# kinesis-advantage-v2_5.net
KiCad netlist of a schematic drawn in EAGLE
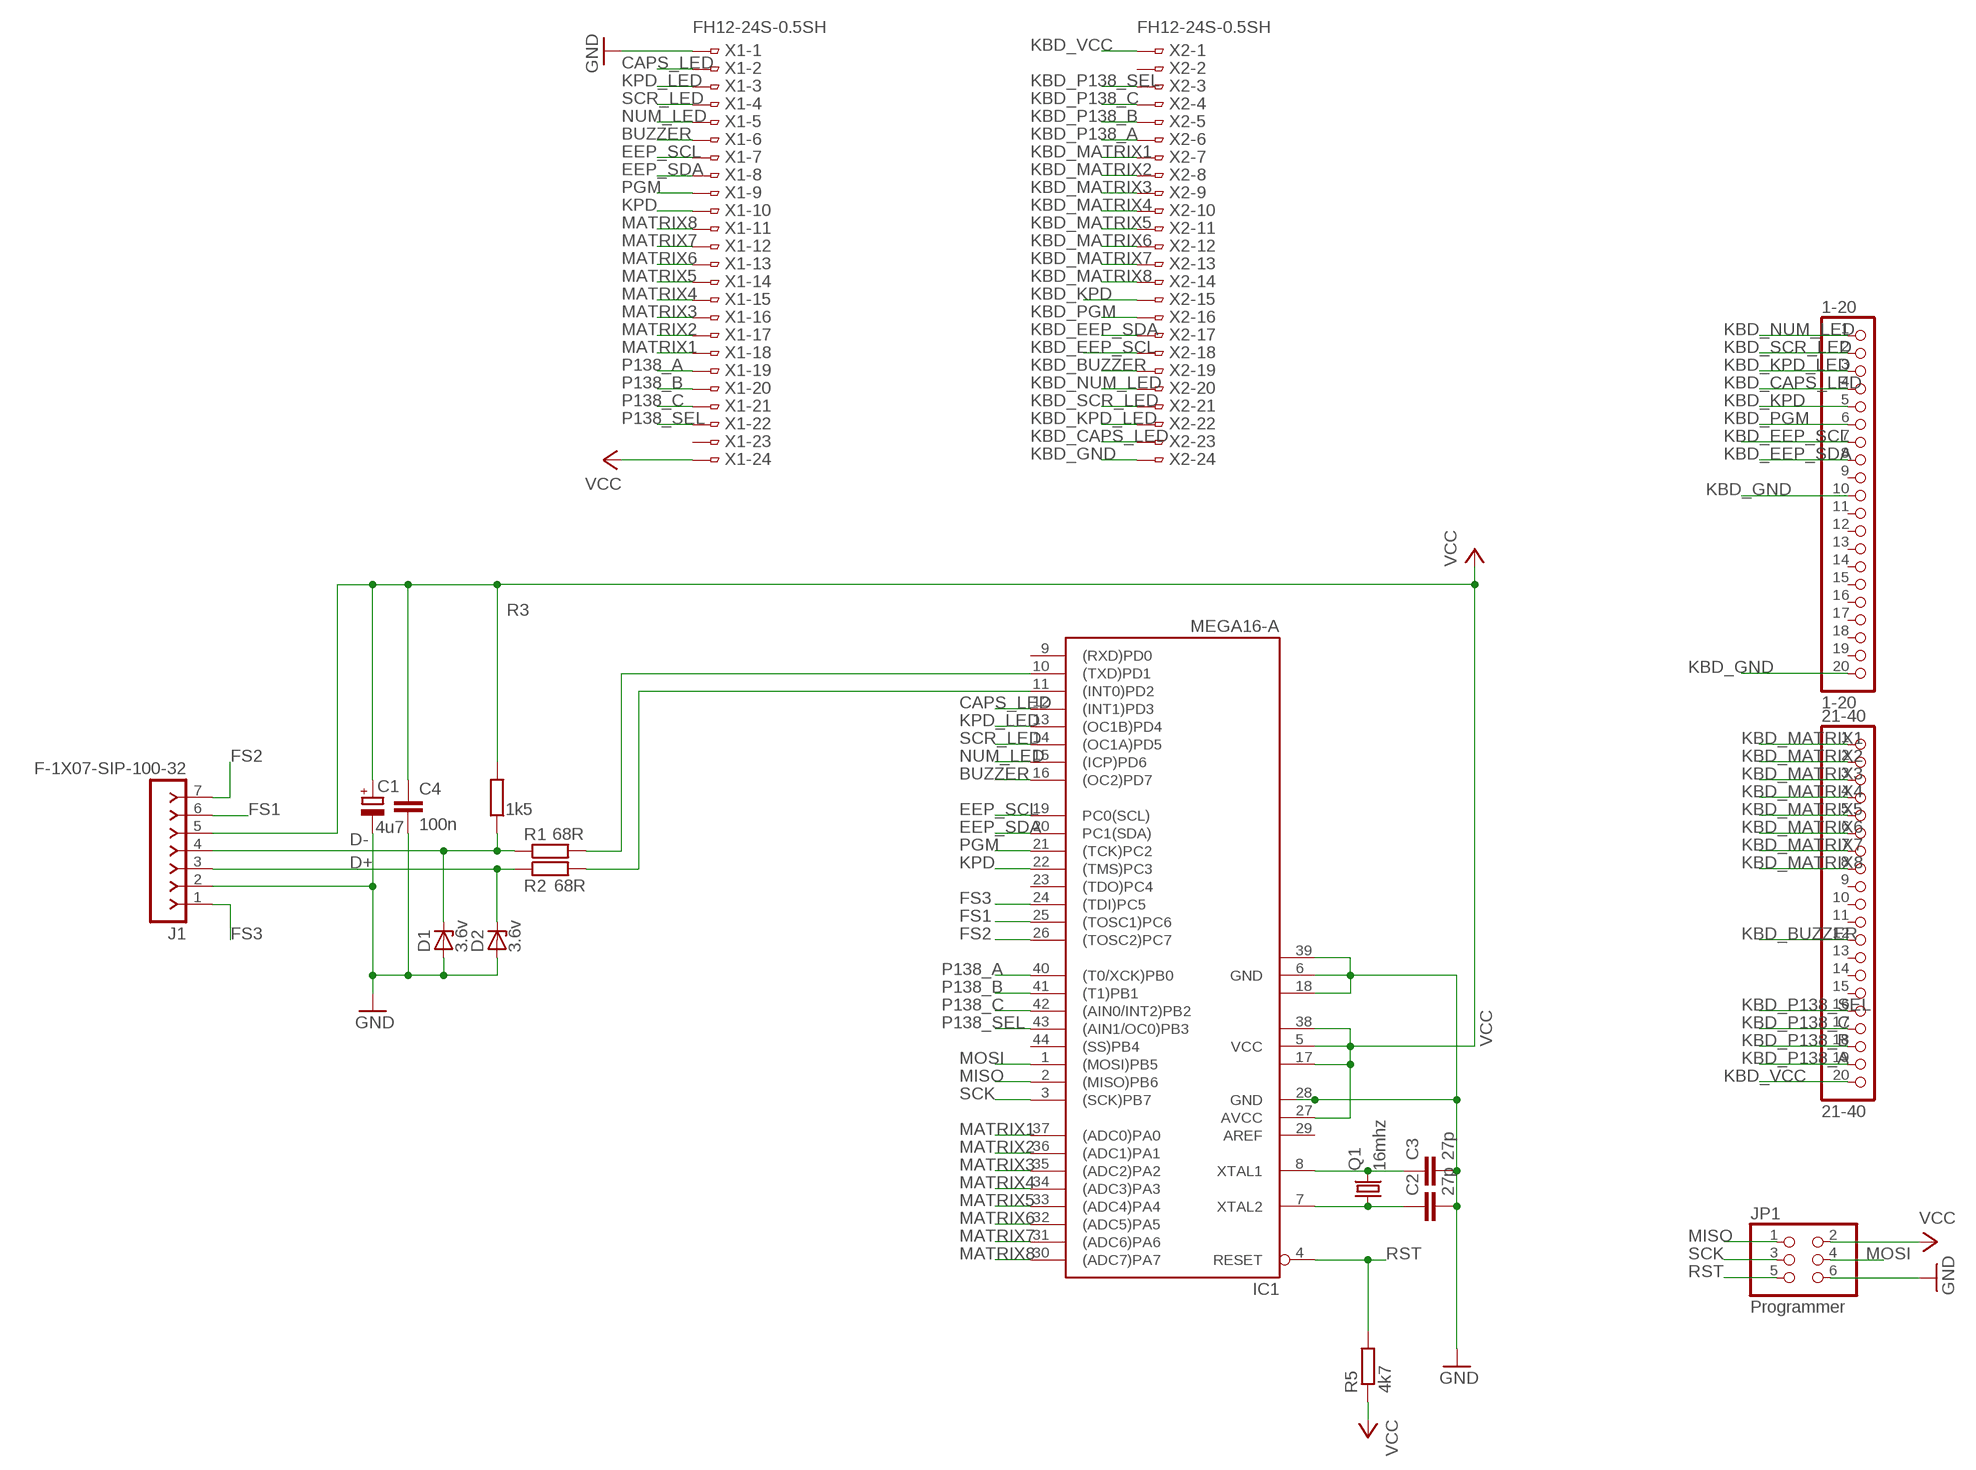
[diagram p0: schematic, sheet 1]

(export (version "E")
  (design (tool "Eeschema 10.0.6"))
  (components
    (comp (ref "1-20")
      (value "1-20")
      (footprint "eagle-import:1X20-BIG")
      (libsource (lib "eagle-import") (part "PINHD-1X20-BIG"))
    )
    (comp (ref "21-40")
      (value "21-40")
      (footprint "eagle-import:1X20-BIG")
      (libsource (lib "eagle-import") (part "PINHD-1X20-BIG"))
    )
    (comp (ref "C1")
      (value "4u7")
      (footprint "eagle-import:E2-5")
      (libsource (lib "eagle-import") (part "CPOL-EUE2-5"))
    )
    (comp (ref "C2")
      (value "27p")
      (footprint "eagle-import:C0603")
      (libsource (lib "eagle-import") (part "C-EUC0603"))
    )
    (comp (ref "C3")
      (value "27p")
      (footprint "eagle-import:C0603")
      (libsource (lib "eagle-import") (part "C-EUC0603"))
    )
    (comp (ref "C4")
      (value "100n")
      (footprint "eagle-import:C0603")
      (libsource (lib "eagle-import") (part "C-EUC0603"))
    )
    (comp (ref "D1")
      (value "3.6v")
      (footprint "eagle-import:SOD80C")
      (libsource (lib "eagle-import") (part "ZENER-DIODESOD80C"))
    )
    (comp (ref "D2")
      (value "3.6v")
      (footprint "eagle-import:SOD80C")
      (libsource (lib "eagle-import") (part "ZENER-DIODESOD80C"))
    )
    (comp (ref "IC1")
      (value "MEGA16-A")
      (footprint "eagle-import:TQFP44")
      (fields (field (name "MPN") "ATMEGA16-16AU"))
      (libsource (lib "eagle-import") (part "MEGA16-A"))
    )
    (comp (ref "J1")
      (value "F-1X07-SIP-100-32")
      (footprint "eagle-import:SIP-100-07-32")
      (libsource (lib "eagle-import") (part "F-1X07-SIP-100-32"))
    )
    (comp (ref "JP1")
      (value "Programmer")
      (footprint "eagle-import:2X03")
      (libsource (lib "eagle-import") (part "PINHD-2X3"))
    )
    (comp (ref "Q1")
      (value "16mhz")
      (footprint "eagle-import:HC49_S")
      (libsource (lib "eagle-import") (part "CRYSTALHC49S"))
    )
    (comp (ref "R1")
      (value "68R")
      (footprint "eagle-import:R0603")
      (libsource (lib "eagle-import") (part "R-EU_R0603"))
    )
    (comp (ref "R2")
      (value "68R")
      (footprint "eagle-import:R0603")
      (libsource (lib "eagle-import") (part "R-EU_R0603"))
    )
    (comp (ref "R3")
      (value "1k5")
      (footprint "eagle-import:R0603")
      (libsource (lib "eagle-import") (part "R-EU_R0603"))
    )
    (comp (ref "R5")
      (value "4k7")
      (footprint "eagle-import:R0603")
      (libsource (lib "eagle-import") (part "R-EU_R0603"))
    )
    (comp (ref "X1")
      (value "FH12-24S-0.5SH")
      (footprint "eagle-import:FH12-24S-0.5SH")
      (fields (field (name "MPN") "FH12-24S-0.5SH(55)"))
      (libsource (lib "eagle-import") (part "FH12-24S-0.5SH"))
    )
    (comp (ref "X2")
      (value "FH12-24S-0.5SH")
      (footprint "eagle-import:FH12-24S-0.5SH")
      (fields (field (name "MPN") "FH12-24S-0.5SH(55)"))
      (libsource (lib "eagle-import") (part "FH12-24S-0.5SH"))
    )
  )
  (nets
    (net (code "1") (name "/BUZZER") (class "Default")
      (node (ref "IC1") (pin "16") (pinfunction "(OC2)PD7_16") (pintype "bidirectional"))
      (node (ref "X1") (pin "6") (pinfunction "1_6") (pintype "passive"))
    )
    (net (code "2") (name "/CAPS_LED") (class "Default")
      (node (ref "IC1") (pin "12") (pinfunction "(INT1)PD3_12") (pintype "bidirectional"))
      (node (ref "X1") (pin "2") (pinfunction "1_2") (pintype "passive"))
    )
    (net (code "3") (name "/D+") (class "Default")
      (node (ref "D2") (pin "C") (pinfunction "C_C") (pintype "passive"))
      (node (ref "J1") (pin "3") (pinfunction "3_3") (pintype "passive"))
      (node (ref "R2") (pin "1") (pinfunction "1_1") (pintype "passive"))
    )
    (net (code "4") (name "/D-") (class "Default")
      (node (ref "D1") (pin "C") (pinfunction "C_C") (pintype "passive"))
      (node (ref "J1") (pin "4") (pinfunction "4_4") (pintype "passive"))
      (node (ref "R1") (pin "1") (pinfunction "1_1") (pintype "passive"))
      (node (ref "R3") (pin "1") (pinfunction "1_1") (pintype "passive"))
    )
    (net (code "5") (name "/EEP_SCL") (class "Default")
      (node (ref "IC1") (pin "19") (pinfunction "PC0(SCL)_19") (pintype "bidirectional"))
      (node (ref "X1") (pin "7") (pinfunction "1_7") (pintype "passive"))
    )
    (net (code "6") (name "/EEP_SDA") (class "Default")
      (node (ref "IC1") (pin "20") (pinfunction "PC1(SDA)_20") (pintype "bidirectional"))
      (node (ref "X1") (pin "8") (pinfunction "1_8") (pintype "passive"))
    )
    (net (code "7") (name "/FS1") (class "Default")
      (node (ref "IC1") (pin "25") (pinfunction "(TOSC1)PC6_25") (pintype "bidirectional"))
      (node (ref "J1") (pin "6") (pinfunction "6_6") (pintype "passive"))
    )
    (net (code "8") (name "/FS2") (class "Default")
      (node (ref "IC1") (pin "26") (pinfunction "(TOSC2)PC7_26") (pintype "bidirectional"))
      (node (ref "J1") (pin "7") (pinfunction "7_7") (pintype "passive"))
    )
    (net (code "9") (name "/FS3") (class "Default")
      (node (ref "IC1") (pin "24") (pinfunction "(TDI)PC5_24") (pintype "bidirectional"))
      (node (ref "J1") (pin "1") (pinfunction "1_1") (pintype "passive"))
    )
    (net (code "10") (name "/KBD_BUZZER") (class "Default")
      (node (ref "21-40") (pin "12") (pinfunction "12_12") (pintype "passive"))
      (node (ref "X2") (pin "19") (pinfunction "1_19") (pintype "passive"))
    )
    (net (code "11") (name "/KBD_CAPS_LED") (class "Default")
      (node (ref "1-20") (pin "4") (pinfunction "4_4") (pintype "passive"))
      (node (ref "X2") (pin "23") (pinfunction "1_23") (pintype "passive"))
    )
    (net (code "12") (name "/KBD_EEP_SCL") (class "Default")
      (node (ref "1-20") (pin "7") (pinfunction "7_7") (pintype "passive"))
      (node (ref "X2") (pin "18") (pinfunction "1_18") (pintype "passive"))
    )
    (net (code "13") (name "/KBD_EEP_SDA") (class "Default")
      (node (ref "1-20") (pin "8") (pinfunction "8_8") (pintype "passive"))
      (node (ref "X2") (pin "17") (pinfunction "1_17") (pintype "passive"))
    )
    (net (code "14") (name "/KBD_GND") (class "Default")
      (node (ref "1-20") (pin "10") (pinfunction "10_10") (pintype "passive"))
      (node (ref "1-20") (pin "20") (pinfunction "20_20") (pintype "passive"))
      (node (ref "X2") (pin "24") (pinfunction "1_24") (pintype "passive"))
    )
    (net (code "15") (name "/KBD_KPD") (class "Default")
      (node (ref "1-20") (pin "5") (pinfunction "5_5") (pintype "passive"))
      (node (ref "X2") (pin "15") (pinfunction "1_15") (pintype "passive"))
    )
    (net (code "16") (name "/KBD_KPD_LED") (class "Default")
      (node (ref "1-20") (pin "3") (pinfunction "3_3") (pintype "passive"))
      (node (ref "X2") (pin "22") (pinfunction "1_22") (pintype "passive"))
    )
    (net (code "17") (name "/KBD_MATRIX1") (class "Default")
      (node (ref "21-40") (pin "1") (pinfunction "1_1") (pintype "passive"))
      (node (ref "X2") (pin "7") (pinfunction "1_7") (pintype "passive"))
    )
    (net (code "18") (name "/KBD_MATRIX2") (class "Default")
      (node (ref "21-40") (pin "2") (pinfunction "2_2") (pintype "passive"))
      (node (ref "X2") (pin "8") (pinfunction "1_8") (pintype "passive"))
    )
    (net (code "19") (name "/KBD_MATRIX3") (class "Default")
      (node (ref "21-40") (pin "3") (pinfunction "3_3") (pintype "passive"))
      (node (ref "X2") (pin "9") (pinfunction "1_9") (pintype "passive"))
    )
    (net (code "20") (name "/KBD_MATRIX4") (class "Default")
      (node (ref "21-40") (pin "4") (pinfunction "4_4") (pintype "passive"))
      (node (ref "X2") (pin "10") (pinfunction "1_10") (pintype "passive"))
    )
    (net (code "21") (name "/KBD_MATRIX5") (class "Default")
      (node (ref "21-40") (pin "5") (pinfunction "5_5") (pintype "passive"))
      (node (ref "X2") (pin "11") (pinfunction "1_11") (pintype "passive"))
    )
    (net (code "22") (name "/KBD_MATRIX6") (class "Default")
      (node (ref "21-40") (pin "6") (pinfunction "6_6") (pintype "passive"))
      (node (ref "X2") (pin "12") (pinfunction "1_12") (pintype "passive"))
    )
    (net (code "23") (name "/KBD_MATRIX7") (class "Default")
      (node (ref "21-40") (pin "7") (pinfunction "7_7") (pintype "passive"))
      (node (ref "X2") (pin "13") (pinfunction "1_13") (pintype "passive"))
    )
    (net (code "24") (name "/KBD_MATRIX8") (class "Default")
      (node (ref "21-40") (pin "8") (pinfunction "8_8") (pintype "passive"))
      (node (ref "X2") (pin "14") (pinfunction "1_14") (pintype "passive"))
    )
    (net (code "25") (name "/KBD_NUM_LED") (class "Default")
      (node (ref "1-20") (pin "1") (pinfunction "1_1") (pintype "passive"))
      (node (ref "X2") (pin "20") (pinfunction "1_20") (pintype "passive"))
    )
    (net (code "26") (name "/KBD_P138_A") (class "Default")
      (node (ref "21-40") (pin "19") (pinfunction "19_19") (pintype "passive"))
      (node (ref "X2") (pin "6") (pinfunction "1_6") (pintype "passive"))
    )
    (net (code "27") (name "/KBD_P138_B") (class "Default")
      (node (ref "21-40") (pin "18") (pinfunction "18_18") (pintype "passive"))
      (node (ref "X2") (pin "5") (pinfunction "1_5") (pintype "passive"))
    )
    (net (code "28") (name "/KBD_P138_C") (class "Default")
      (node (ref "21-40") (pin "17") (pinfunction "17_17") (pintype "passive"))
      (node (ref "X2") (pin "4") (pinfunction "1_4") (pintype "passive"))
    )
    (net (code "29") (name "/KBD_P138_SEL") (class "Default")
      (node (ref "21-40") (pin "16") (pinfunction "16_16") (pintype "passive"))
      (node (ref "X2") (pin "3") (pinfunction "1_3") (pintype "passive"))
    )
    (net (code "30") (name "/KBD_PGM") (class "Default")
      (node (ref "1-20") (pin "6") (pinfunction "6_6") (pintype "passive"))
      (node (ref "X2") (pin "16") (pinfunction "1_16") (pintype "passive"))
    )
    (net (code "31") (name "/KBD_SCR_LED") (class "Default")
      (node (ref "1-20") (pin "2") (pinfunction "2_2") (pintype "passive"))
      (node (ref "X2") (pin "21") (pinfunction "1_21") (pintype "passive"))
    )
    (net (code "32") (name "/KBD_VCC") (class "Default")
      (node (ref "21-40") (pin "20") (pinfunction "20_20") (pintype "passive"))
      (node (ref "X2") (pin "1") (pinfunction "1_1") (pintype "passive"))
    )
    (net (code "33") (name "/KPD") (class "Default")
      (node (ref "IC1") (pin "22") (pinfunction "(TMS)PC3_22") (pintype "bidirectional"))
      (node (ref "X1") (pin "10") (pinfunction "1_10") (pintype "passive"))
    )
    (net (code "34") (name "/KPD_LED") (class "Default")
      (node (ref "IC1") (pin "13") (pinfunction "(OC1B)PD4_13") (pintype "bidirectional"))
      (node (ref "X1") (pin "3") (pinfunction "1_3") (pintype "passive"))
    )
    (net (code "35") (name "/MATRIX1") (class "Default")
      (node (ref "IC1") (pin "37") (pinfunction "(ADC0)PA0_37") (pintype "bidirectional"))
      (node (ref "X1") (pin "18") (pinfunction "1_18") (pintype "passive"))
    )
    (net (code "36") (name "/MATRIX2") (class "Default")
      (node (ref "IC1") (pin "36") (pinfunction "(ADC1)PA1_36") (pintype "bidirectional"))
      (node (ref "X1") (pin "17") (pinfunction "1_17") (pintype "passive"))
    )
    (net (code "37") (name "/MATRIX3") (class "Default")
      (node (ref "IC1") (pin "35") (pinfunction "(ADC2)PA2_35") (pintype "bidirectional"))
      (node (ref "X1") (pin "16") (pinfunction "1_16") (pintype "passive"))
    )
    (net (code "38") (name "/MATRIX4") (class "Default")
      (node (ref "IC1") (pin "34") (pinfunction "(ADC3)PA3_34") (pintype "bidirectional"))
      (node (ref "X1") (pin "15") (pinfunction "1_15") (pintype "passive"))
    )
    (net (code "39") (name "/MATRIX5") (class "Default")
      (node (ref "IC1") (pin "33") (pinfunction "(ADC4)PA4_33") (pintype "bidirectional"))
      (node (ref "X1") (pin "14") (pinfunction "1_14") (pintype "passive"))
    )
    (net (code "40") (name "/MATRIX6") (class "Default")
      (node (ref "IC1") (pin "32") (pinfunction "(ADC5)PA5_32") (pintype "bidirectional"))
      (node (ref "X1") (pin "13") (pinfunction "1_13") (pintype "passive"))
    )
    (net (code "41") (name "/MATRIX7") (class "Default")
      (node (ref "IC1") (pin "31") (pinfunction "(ADC6)PA6_31") (pintype "bidirectional"))
      (node (ref "X1") (pin "12") (pinfunction "1_12") (pintype "passive"))
    )
    (net (code "42") (name "/MATRIX8") (class "Default")
      (node (ref "IC1") (pin "30") (pinfunction "(ADC7)PA7_30") (pintype "bidirectional"))
      (node (ref "X1") (pin "11") (pinfunction "1_11") (pintype "passive"))
    )
    (net (code "43") (name "/MISO") (class "Default")
      (node (ref "IC1") (pin "2") (pinfunction "(MISO)PB6_2") (pintype "bidirectional"))
      (node (ref "JP1") (pin "1") (pinfunction "1_1") (pintype "passive"))
    )
    (net (code "44") (name "/MOSI") (class "Default")
      (node (ref "IC1") (pin "1") (pinfunction "(MOSI)PB5_1") (pintype "bidirectional"))
      (node (ref "JP1") (pin "4") (pinfunction "4_4") (pintype "passive"))
    )
    (net (code "45") (name "/NUM_LED") (class "Default")
      (node (ref "IC1") (pin "15") (pinfunction "(ICP)PD6_15") (pintype "bidirectional"))
      (node (ref "X1") (pin "5") (pinfunction "1_5") (pintype "passive"))
    )
    (net (code "46") (name "/P138_A") (class "Default")
      (node (ref "IC1") (pin "40") (pinfunction "(T0/XCK)PB0_40") (pintype "bidirectional"))
      (node (ref "X1") (pin "19") (pinfunction "1_19") (pintype "passive"))
    )
    (net (code "47") (name "/P138_B") (class "Default")
      (node (ref "IC1") (pin "41") (pinfunction "(T1)PB1_41") (pintype "bidirectional"))
      (node (ref "X1") (pin "20") (pinfunction "1_20") (pintype "passive"))
    )
    (net (code "48") (name "/P138_C") (class "Default")
      (node (ref "IC1") (pin "42") (pinfunction "(AIN0/INT2)PB2_42") (pintype "bidirectional"))
      (node (ref "X1") (pin "21") (pinfunction "1_21") (pintype "passive"))
    )
    (net (code "49") (name "/P138_SEL") (class "Default")
      (node (ref "IC1") (pin "43") (pinfunction "(AIN1/OC0)PB3_43") (pintype "bidirectional"))
      (node (ref "X1") (pin "22") (pinfunction "1_22") (pintype "passive"))
    )
    (net (code "50") (name "/PGM") (class "Default")
      (node (ref "IC1") (pin "21") (pinfunction "(TCK)PC2_21") (pintype "bidirectional"))
      (node (ref "X1") (pin "9") (pinfunction "1_9") (pintype "passive"))
    )
    (net (code "51") (name "/RST") (class "Default")
      (node (ref "IC1") (pin "4") (pinfunction "RESET_4") (pintype "input"))
      (node (ref "JP1") (pin "5") (pinfunction "5_5") (pintype "passive"))
      (node (ref "R5") (pin "2") (pinfunction "2_2") (pintype "passive"))
    )
    (net (code "52") (name "/SCK") (class "Default")
      (node (ref "IC1") (pin "3") (pinfunction "(SCK)PB7_3") (pintype "bidirectional"))
      (node (ref "JP1") (pin "3") (pinfunction "3_3") (pintype "passive"))
    )
    (net (code "53") (name "/SCR_LED") (class "Default")
      (node (ref "IC1") (pin "14") (pinfunction "(OC1A)PD5_14") (pintype "bidirectional"))
      (node (ref "X1") (pin "4") (pinfunction "1_4") (pintype "passive"))
    )
    (net (code "54") (name "GND") (class "Default")
      (node (ref "C1") (pin "-") (pinfunction "-_-") (pintype "passive"))
      (node (ref "C2") (pin "2") (pinfunction "2_2") (pintype "passive"))
      (node (ref "C3") (pin "2") (pinfunction "2_2") (pintype "passive"))
      (node (ref "C4") (pin "2") (pinfunction "2_2") (pintype "passive"))
      (node (ref "D1") (pin "A") (pinfunction "A_A") (pintype "passive"))
      (node (ref "D2") (pin "A") (pinfunction "A_A") (pintype "passive"))
      (node (ref "IC1") (pin "18") (pinfunction "GND1_18") (pintype "power_in"))
      (node (ref "IC1") (pin "28") (pinfunction "GND_28") (pintype "power_in"))
      (node (ref "IC1") (pin "39") (pinfunction "GND2_39") (pintype "power_in"))
      (node (ref "IC1") (pin "6") (pinfunction "GND_6") (pintype "power_in"))
      (node (ref "J1") (pin "2") (pinfunction "2_2") (pintype "passive"))
      (node (ref "JP1") (pin "6") (pinfunction "6_6") (pintype "passive"))
      (node (ref "X1") (pin "1") (pinfunction "1_1") (pintype "passive"))
    )
    (net (code "55") (name "Net-(IC1-(INT0)PD2)") (class "Default")
      (node (ref "IC1") (pin "11") (pinfunction "(INT0)PD2_11") (pintype "bidirectional"))
      (node (ref "R2") (pin "2") (pinfunction "2_2") (pintype "passive"))
    )
    (net (code "56") (name "Net-(IC1-(TXD)PD1)") (class "Default")
      (node (ref "IC1") (pin "10") (pinfunction "(TXD)PD1_10") (pintype "bidirectional"))
      (node (ref "R1") (pin "2") (pinfunction "2_2") (pintype "passive"))
    )
    (net (code "57") (name "Net-(IC1-XTAL1)") (class "Default")
      (node (ref "C3") (pin "1") (pinfunction "1_1") (pintype "passive"))
      (node (ref "IC1") (pin "8") (pinfunction "XTAL1_8") (pintype "bidirectional"))
      (node (ref "Q1") (pin "2") (pinfunction "2_2") (pintype "passive"))
    )
    (net (code "58") (name "Net-(IC1-XTAL2)") (class "Default")
      (node (ref "C2") (pin "1") (pinfunction "1_1") (pintype "passive"))
      (node (ref "IC1") (pin "7") (pinfunction "XTAL2_7") (pintype "bidirectional"))
      (node (ref "Q1") (pin "1") (pinfunction "1_1") (pintype "passive"))
    )
    (net (code "59") (name "VCC") (class "Default")
      (node (ref "C1") (pin "+") (pinfunction "+_+") (pintype "passive"))
      (node (ref "C4") (pin "1") (pinfunction "1_1") (pintype "passive"))
      (node (ref "IC1") (pin "17") (pinfunction "VCC1_17") (pintype "power_in"))
      (node (ref "IC1") (pin "27") (pinfunction "AVCC_27") (pintype "power_in"))
      (node (ref "IC1") (pin "38") (pinfunction "VCC2_38") (pintype "power_in"))
      (node (ref "IC1") (pin "5") (pinfunction "VCC_5") (pintype "power_in"))
      (node (ref "J1") (pin "5") (pinfunction "5_5") (pintype "passive"))
      (node (ref "JP1") (pin "2") (pinfunction "2_2") (pintype "passive"))
      (node (ref "R3") (pin "2") (pinfunction "2_2") (pintype "passive"))
      (node (ref "R5") (pin "1") (pinfunction "1_1") (pintype "passive"))
      (node (ref "X1") (pin "24") (pinfunction "1_24") (pintype "passive"))
    )
    (net (code "60") (name "unconnected-(1-20-Pad9)") (class "Default")
      (node (ref "1-20") (pin "9") (pinfunction "9_9") (pintype "passive"))
    )
    (net (code "61") (name "unconnected-(1-20-Pad11)") (class "Default")
      (node (ref "1-20") (pin "11") (pinfunction "11_11") (pintype "passive"))
    )
    (net (code "62") (name "unconnected-(1-20-Pad12)") (class "Default")
      (node (ref "1-20") (pin "12") (pinfunction "12_12") (pintype "passive"))
    )
    (net (code "63") (name "unconnected-(1-20-Pad13)") (class "Default")
      (node (ref "1-20") (pin "13") (pinfunction "13_13") (pintype "passive"))
    )
    (net (code "64") (name "unconnected-(1-20-Pad14)") (class "Default")
      (node (ref "1-20") (pin "14") (pinfunction "14_14") (pintype "passive"))
    )
    (net (code "65") (name "unconnected-(1-20-Pad15)") (class "Default")
      (node (ref "1-20") (pin "15") (pinfunction "15_15") (pintype "passive"))
    )
    (net (code "66") (name "unconnected-(1-20-Pad16)") (class "Default")
      (node (ref "1-20") (pin "16") (pinfunction "16_16") (pintype "passive"))
    )
    (net (code "67") (name "unconnected-(1-20-Pad17)") (class "Default")
      (node (ref "1-20") (pin "17") (pinfunction "17_17") (pintype "passive"))
    )
    (net (code "68") (name "unconnected-(1-20-Pad18)") (class "Default")
      (node (ref "1-20") (pin "18") (pinfunction "18_18") (pintype "passive"))
    )
    (net (code "69") (name "unconnected-(1-20-Pad19)") (class "Default")
      (node (ref "1-20") (pin "19") (pinfunction "19_19") (pintype "passive"))
    )
    (net (code "70") (name "unconnected-(21-40-Pad9)") (class "Default")
      (node (ref "21-40") (pin "9") (pinfunction "9_9") (pintype "passive"))
    )
    (net (code "71") (name "unconnected-(21-40-Pad10)") (class "Default")
      (node (ref "21-40") (pin "10") (pinfunction "10_10") (pintype "passive"))
    )
    (net (code "72") (name "unconnected-(21-40-Pad11)") (class "Default")
      (node (ref "21-40") (pin "11") (pinfunction "11_11") (pintype "passive"))
    )
    (net (code "73") (name "unconnected-(21-40-Pad13)") (class "Default")
      (node (ref "21-40") (pin "13") (pinfunction "13_13") (pintype "passive"))
    )
    (net (code "74") (name "unconnected-(21-40-Pad14)") (class "Default")
      (node (ref "21-40") (pin "14") (pinfunction "14_14") (pintype "passive"))
    )
    (net (code "75") (name "unconnected-(21-40-Pad15)") (class "Default")
      (node (ref "21-40") (pin "15") (pinfunction "15_15") (pintype "passive"))
    )
    (net (code "76") (name "unconnected-(IC1-(RXD)PD0-Pad9)") (class "Default")
      (node (ref "IC1") (pin "9") (pinfunction "(RXD)PD0_9") (pintype "bidirectional"))
    )
    (net (code "77") (name "unconnected-(IC1-(SS)PB4-Pad44)") (class "Default")
      (node (ref "IC1") (pin "44") (pinfunction "(SS)PB4_44") (pintype "bidirectional"))
    )
    (net (code "78") (name "unconnected-(IC1-(TDO)PC4-Pad23)") (class "Default")
      (node (ref "IC1") (pin "23") (pinfunction "(TDO)PC4_23") (pintype "bidirectional"))
    )
    (net (code "79") (name "unconnected-(IC1-AREF-Pad29)") (class "Default")
      (node (ref "IC1") (pin "29") (pinfunction "AREF_29") (pintype "passive"))
    )
    (net (code "80") (name "unconnected-(X1P-1-Pad23)") (class "Default")
      (node (ref "X1") (pin "23") (pinfunction "1_23") (pintype "passive"))
    )
    (net (code "81") (name "unconnected-(X2L-1-Pad2)") (class "Default")
      (node (ref "X2") (pin "2") (pinfunction "1_2") (pintype "passive"))
    )
  )
)
